# mouse_v4.net
KiCad netlist of a schematic drawn in EAGLE
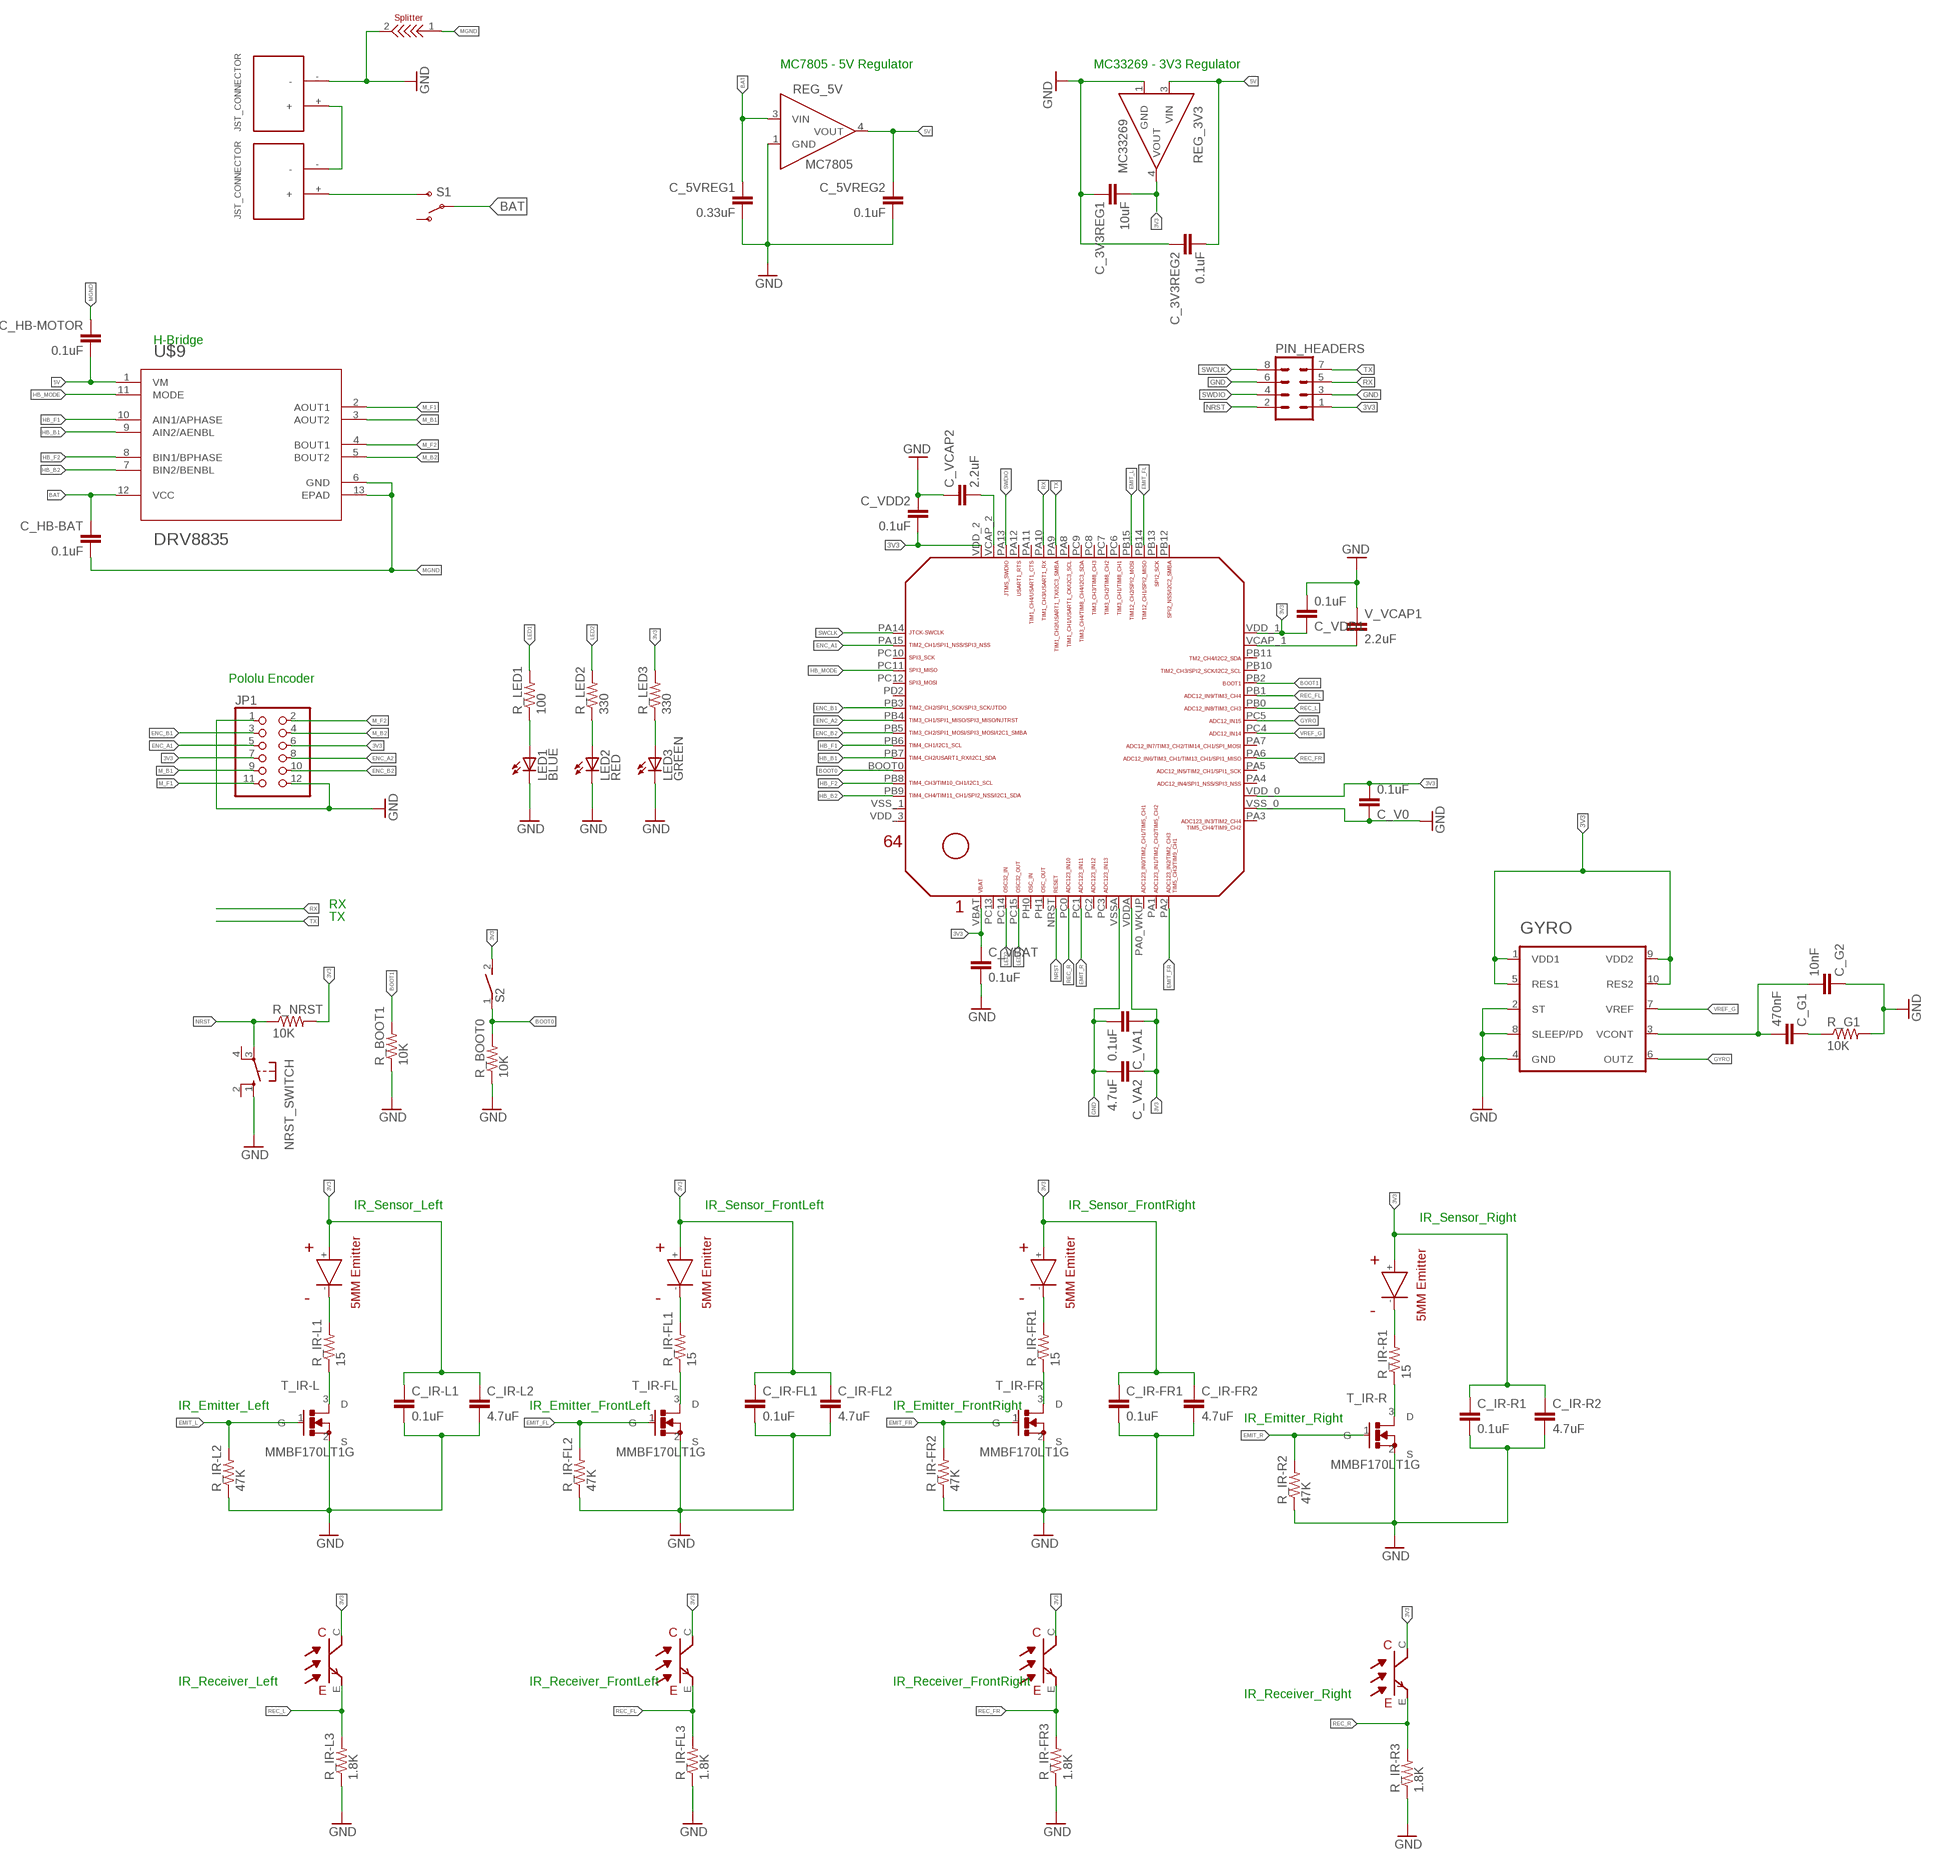
[diagram p0: schematic, sheet 1]

(export (version "E")
  (design (tool "Eeschema 10.0.6"))
  (components
    (comp (ref "C_3V3REG1")
      (value "10uF")
      (footprint "eagle-import:0603-CAP")
      (libsource (lib "eagle-import") (part "CAP0603-CAP"))
    )
    (comp (ref "C_3V3REG2")
      (value "0.1uF")
      (footprint "eagle-import:0603-CAP")
      (libsource (lib "eagle-import") (part "CAP0603-CAP"))
    )
    (comp (ref "C_5VREG1")
      (value "0.33uF")
      (footprint "eagle-import:0603-CAP")
      (libsource (lib "eagle-import") (part "CAP0603-CAP"))
    )
    (comp (ref "C_5VREG2")
      (value "0.1uF")
      (footprint "eagle-import:0603-CAP")
      (libsource (lib "eagle-import") (part "CAP0603-CAP"))
    )
    (comp (ref "C_G1")
      (value "470nF")
      (footprint "eagle-import:0603-CAP")
      (libsource (lib "eagle-import") (part "CAP0603-CAP"))
    )
    (comp (ref "C_G2")
      (value "10nF")
      (footprint "eagle-import:0603-CAP")
      (libsource (lib "eagle-import") (part "CAP0603-CAP"))
    )
    (comp (ref "C_HB-BAT")
      (value "0.1uF")
      (footprint "eagle-import:0603-CAP")
      (libsource (lib "eagle-import") (part "CAP0603-CAP"))
    )
    (comp (ref "C_HB-MOTOR")
      (value "0.1uF")
      (footprint "eagle-import:0603-CAP")
      (libsource (lib "eagle-import") (part "CAP0603-CAP"))
    )
    (comp (ref "C_IR-FL1")
      (value "0.1uF")
      (footprint "eagle-import:0603-CAP")
      (libsource (lib "eagle-import") (part "CAP0603-CAP"))
    )
    (comp (ref "C_IR-FL2")
      (value "4.7uF")
      (footprint "eagle-import:0603-CAP")
      (libsource (lib "eagle-import") (part "CAP0603-CAP"))
    )
    (comp (ref "C_IR-FR1")
      (value "0.1uF")
      (footprint "eagle-import:0603-CAP")
      (libsource (lib "eagle-import") (part "CAP0603-CAP"))
    )
    (comp (ref "C_IR-FR2")
      (value "4.7uF")
      (footprint "eagle-import:0603-CAP")
      (libsource (lib "eagle-import") (part "CAP0603-CAP"))
    )
    (comp (ref "C_IR-L1")
      (value "0.1uF")
      (footprint "eagle-import:0603-CAP")
      (libsource (lib "eagle-import") (part "CAP0603-CAP"))
    )
    (comp (ref "C_IR-L2")
      (value "4.7uF")
      (footprint "eagle-import:0603-CAP")
      (libsource (lib "eagle-import") (part "CAP0603-CAP"))
    )
    (comp (ref "C_IR-R1")
      (value "0.1uF")
      (footprint "eagle-import:0603-CAP")
      (libsource (lib "eagle-import") (part "CAP0603-CAP"))
    )
    (comp (ref "C_IR-R2")
      (value "4.7uF")
      (footprint "eagle-import:0603-CAP")
      (libsource (lib "eagle-import") (part "CAP0603-CAP"))
    )
    (comp (ref "C_V0")
      (value "0.1uF")
      (footprint "eagle-import:0603-CAP")
      (libsource (lib "eagle-import") (part "CAP0603-CAP"))
    )
    (comp (ref "C_VA1")
      (value "0.1uF")
      (footprint "eagle-import:0603-CAP")
      (libsource (lib "eagle-import") (part "CAP0603-CAP"))
    )
    (comp (ref "C_VA2")
      (value "4.7uF")
      (footprint "eagle-import:0603-CAP")
      (libsource (lib "eagle-import") (part "CAP0603-CAP"))
    )
    (comp (ref "C_VBAT")
      (value "0.1uF")
      (footprint "eagle-import:0603-CAP")
      (libsource (lib "eagle-import") (part "CAP0603-CAP"))
    )
    (comp (ref "C_VCAP2")
      (value "2.2uF")
      (footprint "eagle-import:0603-CAP")
      (libsource (lib "eagle-import") (part "CAP0603-CAP"))
    )
    (comp (ref "C_VDD1")
      (value "0.1uF")
      (footprint "eagle-import:0603-CAP")
      (libsource (lib "eagle-import") (part "CAP0603-CAP"))
    )
    (comp (ref "C_VDD2")
      (value "0.1uF")
      (footprint "eagle-import:0603-CAP")
      (libsource (lib "eagle-import") (part "CAP0603-CAP"))
    )
    (comp (ref "GYRO")
      (value "LY3200ALH")
      (footprint "eagle-import:10-TLGA")
      (libsource (lib "eagle-import") (part "LY3200ALH"))
    )
    (comp (ref "IR_FL")
      (value "EMITTER")
      (footprint "eagle-import:EMITTER")
      (libsource (lib "eagle-import") (part "EMITTER"))
    )
    (comp (ref "IR_FR")
      (value "EMITTER")
      (footprint "eagle-import:EMITTER")
      (libsource (lib "eagle-import") (part "EMITTER"))
    )
    (comp (ref "IR_L")
      (value "EMITTER")
      (footprint "eagle-import:EMITTER")
      (libsource (lib "eagle-import") (part "EMITTER"))
    )
    (comp (ref "IR_R")
      (value "EMITTER")
      (footprint "eagle-import:EMITTER")
      (libsource (lib "eagle-import") (part "EMITTER"))
    )
    (comp (ref "JP1")
      (value "PINHD-2X6")
      (footprint "eagle-import:2X06")
      (libsource (lib "eagle-import") (part "PINHD-2X6"))
    )
    (comp (ref "LED1")
      (value "BLUE")
      (footprint "eagle-import:CHIPLED_0603")
      (libsource (lib "eagle-import") (part "LEDCHIPLED_0603"))
    )
    (comp (ref "LED2")
      (value "RED")
      (footprint "eagle-import:CHIPLED_0603")
      (libsource (lib "eagle-import") (part "LEDCHIPLED_0603"))
    )
    (comp (ref "LED3")
      (value "GREEN")
      (footprint "eagle-import:CHIPLED_0603")
      (libsource (lib "eagle-import") (part "LEDCHIPLED_0603"))
    )
    (comp (ref "NRST_SWITCH")
      (value "10-XX")
      (footprint "eagle-import:B3F-10XX")
      (fields (field (name "MPN") "B3F-1000"))
      (libsource (lib "eagle-import") (part "10-XX"))
    )
    (comp (ref "PIN_HEADERS")
      (value "MA04-2")
      (footprint "eagle-import:MA04-2")
      (libsource (lib "eagle-import") (part "MA04-2"))
    )
    (comp (ref "REG_3V3")
      (value "MC33269")
      (footprint "eagle-import:TO-252-3")
      (libsource (lib "eagle-import") (part "MC33269"))
    )
    (comp (ref "REG_5V")
      (value "MC7805")
      (footprint "eagle-import:TO-252-3")
      (libsource (lib "eagle-import") (part "MC7805"))
    )
    (comp (ref "R_BOOT0")
      (value "10K")
      (footprint "eagle-import:0603-RES")
      (libsource (lib "eagle-import") (part "1.8KOHM1/10W1%(0603)"))
    )
    (comp (ref "R_BOOT1")
      (value "10K")
      (footprint "eagle-import:0603-RES")
      (libsource (lib "eagle-import") (part "1.8KOHM1/10W1%(0603)"))
    )
    (comp (ref "R_G1")
      (value "10K")
      (footprint "eagle-import:0603-RES")
      (libsource (lib "eagle-import") (part "1.8KOHM1/10W1%(0603)"))
    )
    (comp (ref "R_IR-FL1")
      (value "15")
      (footprint "eagle-import:0603-RES")
      (libsource (lib "eagle-import") (part "1.8KOHM1/10W1%(0603)"))
    )
    (comp (ref "R_IR-FL2")
      (value "47K")
      (footprint "eagle-import:0603-RES")
      (libsource (lib "eagle-import") (part "1.8KOHM1/10W1%(0603)"))
    )
    (comp (ref "R_IR-FL3")
      (value "1.8K")
      (footprint "eagle-import:0603-RES")
      (libsource (lib "eagle-import") (part "1.8KOHM1/10W1%(0603)"))
    )
    (comp (ref "R_IR-FR1")
      (value "15")
      (footprint "eagle-import:0603-RES")
      (libsource (lib "eagle-import") (part "1.8KOHM1/10W1%(0603)"))
    )
    (comp (ref "R_IR-FR2")
      (value "47K")
      (footprint "eagle-import:0603-RES")
      (libsource (lib "eagle-import") (part "1.8KOHM1/10W1%(0603)"))
    )
    (comp (ref "R_IR-FR3")
      (value "1.8K")
      (footprint "eagle-import:0603-RES")
      (libsource (lib "eagle-import") (part "1.8KOHM1/10W1%(0603)"))
    )
    (comp (ref "R_IR-L1")
      (value "15")
      (footprint "eagle-import:0603-RES")
      (libsource (lib "eagle-import") (part "1.8KOHM1/10W1%(0603)"))
    )
    (comp (ref "R_IR-L2")
      (value "47K")
      (footprint "eagle-import:0603-RES")
      (libsource (lib "eagle-import") (part "1.8KOHM1/10W1%(0603)"))
    )
    (comp (ref "R_IR-L3")
      (value "1.8K")
      (footprint "eagle-import:0603-RES")
      (libsource (lib "eagle-import") (part "1.8KOHM1/10W1%(0603)"))
    )
    (comp (ref "R_IR-R1")
      (value "15")
      (footprint "eagle-import:0603-RES")
      (libsource (lib "eagle-import") (part "1.8KOHM1/10W1%(0603)"))
    )
    (comp (ref "R_IR-R2")
      (value "47K")
      (footprint "eagle-import:0603-RES")
      (libsource (lib "eagle-import") (part "1.8KOHM1/10W1%(0603)"))
    )
    (comp (ref "R_IR-R3")
      (value "1.8K")
      (footprint "eagle-import:0603-RES")
      (libsource (lib "eagle-import") (part "1.8KOHM1/10W1%(0603)"))
    )
    (comp (ref "R_LED1")
      (value "100")
      (footprint "eagle-import:0603-RES")
      (libsource (lib "eagle-import") (part "1.8KOHM1/10W1%(0603)"))
    )
    (comp (ref "R_LED2")
      (value "330")
      (footprint "eagle-import:0603-RES")
      (libsource (lib "eagle-import") (part "1.8KOHM1/10W1%(0603)"))
    )
    (comp (ref "R_LED3")
      (value "330")
      (footprint "eagle-import:0603-RES")
      (libsource (lib "eagle-import") (part "1.8KOHM1/10W1%(0603)"))
    )
    (comp (ref "R_NRST")
      (value "10K")
      (footprint "eagle-import:0603-RES")
      (libsource (lib "eagle-import") (part "1.8KOHM1/10W1%(0603)"))
    )
    (comp (ref "S1")
      (value "SWITCH-SPSTKIT")
      (footprint "eagle-import:SWITCH-SPDT_KIT")
      (libsource (lib "eagle-import") (part "SWITCH-SPSTKIT"))
    )
    (comp (ref "S2")
      (value "DS01E")
      (footprint "eagle-import:DS-01")
      (libsource (lib "eagle-import") (part "DS01E"))
    )
    (comp (ref "T_IR-FL")
      (value "MMBF170LT1G")
      (footprint "eagle-import:SOT-23")
      (libsource (lib "eagle-import") (part "MMBF170LT1G"))
    )
    (comp (ref "T_IR-FR")
      (value "MMBF170LT1G")
      (footprint "eagle-import:SOT-23")
      (libsource (lib "eagle-import") (part "MMBF170LT1G"))
    )
    (comp (ref "T_IR-L")
      (value "MMBF170LT1G")
      (footprint "eagle-import:SOT-23")
      (libsource (lib "eagle-import") (part "MMBF170LT1G"))
    )
    (comp (ref "T_IR-R")
      (value "MMBF170LT1G")
      (footprint "eagle-import:SOT-23")
      (libsource (lib "eagle-import") (part "MMBF170LT1G"))
    )
    (comp (ref "U$1")
      (value "STM32F405/415_LQFP64")
      (footprint "eagle-import:STM32F405_415_LQFP64")
      (libsource (lib "eagle-import") (part "STM32F405/415_LQFP64"))
    )
    (comp (ref "U$2")
      (value "JST_CONNECTOR_FEMALE")
      (footprint "eagle-import:JST_CONNECTOR_FEMALE")
      (libsource (lib "eagle-import") (part "JST_CONNECTOR_FEMALE"))
    )
    (comp (ref "U$3")
      (value "JST_CONNECTOR_FEMALE")
      (footprint "eagle-import:JST_CONNECTOR_FEMALE")
      (libsource (lib "eagle-import") (part "JST_CONNECTOR_FEMALE"))
    )
    (comp (ref "U$4")
      (value "RECEIVER")
      (footprint "eagle-import:RECEIVER")
      (libsource (lib "eagle-import") (part "RECEIVER"))
    )
    (comp (ref "U$5")
      (value "RECEIVER")
      (footprint "eagle-import:RECEIVER")
      (libsource (lib "eagle-import") (part "RECEIVER"))
    )
    (comp (ref "U$6")
      (value "RECEIVER")
      (footprint "eagle-import:RECEIVER")
      (libsource (lib "eagle-import") (part "RECEIVER"))
    )
    (comp (ref "U$7")
      (value "RECEIVER")
      (footprint "eagle-import:RECEIVER")
      (libsource (lib "eagle-import") (part "RECEIVER"))
    )
    (comp (ref "U$8")
      (value "SPLITTER")
      (footprint "eagle-import:SPLITTER")
      (libsource (lib "eagle-import") (part "SPLITTER"))
    )
    (comp (ref "U$9")
      (value "DRV8835")
      (footprint "eagle-import:12-WFDFN")
      (libsource (lib "eagle-import") (part "DRV8835"))
    )
    (comp (ref "V_VCAP1")
      (value "2.2uF")
      (footprint "eagle-import:0603-CAP")
      (libsource (lib "eagle-import") (part "CAP0603-CAP"))
    )
  )
  (nets
    (net (code "1") (name "3V3") (class "Default")
      (node (ref "C_3V3REG1") (pin "2") (pinfunction "2_2") (pintype "passive"))
      (node (ref "C_IR-FL1") (pin "1") (pinfunction "1_1") (pintype "passive"))
      (node (ref "C_IR-FL2") (pin "1") (pinfunction "1_1") (pintype "passive"))
      (node (ref "C_IR-FR1") (pin "1") (pinfunction "1_1") (pintype "passive"))
      (node (ref "C_IR-FR2") (pin "1") (pinfunction "1_1") (pintype "passive"))
      (node (ref "C_IR-L1") (pin "1") (pinfunction "1_1") (pintype "passive"))
      (node (ref "C_IR-L2") (pin "1") (pinfunction "1_1") (pintype "passive"))
      (node (ref "C_IR-R1") (pin "1") (pinfunction "1_1") (pintype "passive"))
      (node (ref "C_IR-R2") (pin "1") (pinfunction "1_1") (pintype "passive"))
      (node (ref "C_V0") (pin "2") (pinfunction "2_2") (pintype "passive"))
      (node (ref "C_VA1") (pin "1") (pinfunction "1_1") (pintype "passive"))
      (node (ref "C_VA2") (pin "1") (pinfunction "1_1") (pintype "passive"))
      (node (ref "C_VBAT") (pin "1") (pinfunction "1_1") (pintype "passive"))
      (node (ref "C_VDD1") (pin "1") (pinfunction "1_1") (pintype "passive"))
      (node (ref "C_VDD2") (pin "2") (pinfunction "2_2") (pintype "passive"))
      (node (ref "GYRO") (pin "1") (pinfunction "VDD1_1") (pintype "bidirectional"))
      (node (ref "GYRO") (pin "10") (pinfunction "RES2_10") (pintype "bidirectional"))
      (node (ref "GYRO") (pin "5") (pinfunction "RES1_5") (pintype "bidirectional"))
      (node (ref "GYRO") (pin "9") (pinfunction "VDD2_9") (pintype "bidirectional"))
      (node (ref "IR_FL") (pin "+") (pinfunction "+_+") (pintype "bidirectional"))
      (node (ref "IR_FR") (pin "+") (pinfunction "+_+") (pintype "bidirectional"))
      (node (ref "IR_L") (pin "+") (pinfunction "+_+") (pintype "bidirectional"))
      (node (ref "IR_R") (pin "+") (pinfunction "+_+") (pintype "bidirectional"))
      (node (ref "JP1") (pin "6") (pinfunction "6_6") (pintype "passive"))
      (node (ref "JP1") (pin "7") (pinfunction "7_7") (pintype "passive"))
      (node (ref "PIN_HEADERS") (pin "1") (pinfunction "1_1") (pintype "passive"))
      (node (ref "REG_3V3") (pin "4") (pinfunction "VOUT_4") (pintype "bidirectional"))
      (node (ref "R_LED3") (pin "2") (pinfunction "2_2") (pintype "passive"))
      (node (ref "R_NRST") (pin "2") (pinfunction "2_2") (pintype "passive"))
      (node (ref "S2") (pin "2") (pinfunction "2_2") (pintype "passive"))
      (node (ref "U$1") (pin "VBAT") (pinfunction "VBAT_VBAT") (pintype "bidirectional"))
      (node (ref "U$1") (pin "VDDA") (pinfunction "VDDA_VDDA") (pintype "bidirectional"))
      (node (ref "U$1") (pin "VDD_0") (pinfunction "VDD_0_VDD_0") (pintype "bidirectional"))
      (node (ref "U$1") (pin "VDD_1") (pinfunction "VDD_1_VDD_1") (pintype "bidirectional"))
      (node (ref "U$1") (pin "VDD_2") (pinfunction "VDD_2_VDD_2") (pintype "bidirectional"))
      (node (ref "U$4") (pin "C") (pinfunction "C_C") (pintype "bidirectional"))
      (node (ref "U$5") (pin "C") (pinfunction "C_C") (pintype "bidirectional"))
      (node (ref "U$6") (pin "C") (pinfunction "C_C") (pintype "bidirectional"))
      (node (ref "U$7") (pin "C") (pinfunction "C_C") (pintype "bidirectional"))
    )
    (net (code "2") (name "5V") (class "Default")
      (node (ref "C_3V3REG2") (pin "2") (pinfunction "2_2") (pintype "passive"))
      (node (ref "C_5VREG2") (pin "1") (pinfunction "1_1") (pintype "passive"))
      (node (ref "C_HB-MOTOR") (pin "2") (pinfunction "2_2") (pintype "passive"))
      (node (ref "REG_3V3") (pin "3") (pinfunction "VIN_3") (pintype "bidirectional"))
      (node (ref "REG_5V") (pin "4") (pinfunction "VOUT_4") (pintype "bidirectional"))
      (node (ref "U$9") (pin "1") (pinfunction "VM_1") (pintype "bidirectional"))
    )
    (net (code "3") (name "BAT") (class "Default")
      (node (ref "C_5VREG1") (pin "1") (pinfunction "1_1") (pintype "passive"))
      (node (ref "C_HB-BAT") (pin "1") (pinfunction "1_1") (pintype "passive"))
      (node (ref "REG_5V") (pin "3") (pinfunction "VIN_3") (pintype "bidirectional"))
      (node (ref "S1") (pin "2") (pinfunction "P_2") (pintype "passive"))
      (node (ref "U$9") (pin "12") (pinfunction "VCC_12") (pintype "bidirectional"))
    )
    (net (code "4") (name "BOOT0") (class "Default")
      (node (ref "R_BOOT0") (pin "2") (pinfunction "2_2") (pintype "passive"))
      (node (ref "S2") (pin "1") (pinfunction "1_1") (pintype "passive"))
      (node (ref "U$1") (pin "BOOT0") (pinfunction "BOOT0_BOOT0") (pintype "bidirectional"))
    )
    (net (code "5") (name "BOOT1") (class "Default")
      (node (ref "R_BOOT1") (pin "2") (pinfunction "2_2") (pintype "passive"))
      (node (ref "U$1") (pin "PB2") (pinfunction "PB2_PB2") (pintype "bidirectional"))
    )
    (net (code "6") (name "EMIT_FL") (class "Default")
      (node (ref "R_IR-FL2") (pin "2") (pinfunction "2_2") (pintype "passive"))
      (node (ref "T_IR-FL") (pin "1") (pinfunction "G_1") (pintype "passive"))
      (node (ref "U$1") (pin "PB14") (pinfunction "PB14_PB14") (pintype "bidirectional"))
    )
    (net (code "7") (name "EMIT_FR") (class "Default")
      (node (ref "R_IR-FR2") (pin "2") (pinfunction "2_2") (pintype "passive"))
      (node (ref "T_IR-FR") (pin "1") (pinfunction "G_1") (pintype "passive"))
      (node (ref "U$1") (pin "PA2") (pinfunction "PA2_PA2") (pintype "bidirectional"))
    )
    (net (code "8") (name "EMIT_L") (class "Default")
      (node (ref "R_IR-L2") (pin "2") (pinfunction "2_2") (pintype "passive"))
      (node (ref "T_IR-L") (pin "1") (pinfunction "G_1") (pintype "passive"))
      (node (ref "U$1") (pin "PB15") (pinfunction "PB15_PB15") (pintype "bidirectional"))
    )
    (net (code "9") (name "EMIT_R") (class "Default")
      (node (ref "R_IR-R2") (pin "2") (pinfunction "2_2") (pintype "passive"))
      (node (ref "T_IR-R") (pin "1") (pinfunction "G_1") (pintype "passive"))
      (node (ref "U$1") (pin "PC1") (pinfunction "PC1_PC1") (pintype "bidirectional"))
    )
    (net (code "10") (name "ENC_A1") (class "Default")
      (node (ref "JP1") (pin "5") (pinfunction "5_5") (pintype "passive"))
      (node (ref "U$1") (pin "PA15") (pinfunction "PA15_PA15") (pintype "bidirectional"))
    )
    (net (code "11") (name "ENC_A2") (class "Default")
      (node (ref "JP1") (pin "8") (pinfunction "8_8") (pintype "passive"))
      (node (ref "U$1") (pin "PB4") (pinfunction "PB4_PB4") (pintype "bidirectional"))
    )
    (net (code "12") (name "ENC_B1") (class "Default")
      (node (ref "JP1") (pin "3") (pinfunction "3_3") (pintype "passive"))
      (node (ref "U$1") (pin "PB3") (pinfunction "PB3_PB3") (pintype "bidirectional"))
    )
    (net (code "13") (name "ENC_B2") (class "Default")
      (node (ref "JP1") (pin "10") (pinfunction "10_10") (pintype "passive"))
      (node (ref "U$1") (pin "PB5") (pinfunction "PB5_PB5") (pintype "bidirectional"))
    )
    (net (code "14") (name "GND") (class "Default")
      (node (ref "C_3V3REG1") (pin "1") (pinfunction "1_1") (pintype "passive"))
      (node (ref "C_3V3REG2") (pin "1") (pinfunction "1_1") (pintype "passive"))
      (node (ref "C_5VREG1") (pin "2") (pinfunction "2_2") (pintype "passive"))
      (node (ref "C_5VREG2") (pin "2") (pinfunction "2_2") (pintype "passive"))
      (node (ref "C_G2") (pin "1") (pinfunction "1_1") (pintype "passive"))
      (node (ref "C_IR-FL1") (pin "2") (pinfunction "2_2") (pintype "passive"))
      (node (ref "C_IR-FL2") (pin "2") (pinfunction "2_2") (pintype "passive"))
      (node (ref "C_IR-FR1") (pin "2") (pinfunction "2_2") (pintype "passive"))
      (node (ref "C_IR-FR2") (pin "2") (pinfunction "2_2") (pintype "passive"))
      (node (ref "C_IR-L1") (pin "2") (pinfunction "2_2") (pintype "passive"))
      (node (ref "C_IR-L2") (pin "2") (pinfunction "2_2") (pintype "passive"))
      (node (ref "C_IR-R1") (pin "2") (pinfunction "2_2") (pintype "passive"))
      (node (ref "C_IR-R2") (pin "2") (pinfunction "2_2") (pintype "passive"))
      (node (ref "C_V0") (pin "1") (pinfunction "1_1") (pintype "passive"))
      (node (ref "C_VA1") (pin "2") (pinfunction "2_2") (pintype "passive"))
      (node (ref "C_VA2") (pin "2") (pinfunction "2_2") (pintype "passive"))
      (node (ref "C_VBAT") (pin "2") (pinfunction "2_2") (pintype "passive"))
      (node (ref "C_VCAP2") (pin "1") (pinfunction "1_1") (pintype "passive"))
      (node (ref "C_VDD1") (pin "2") (pinfunction "2_2") (pintype "passive"))
      (node (ref "C_VDD2") (pin "1") (pinfunction "1_1") (pintype "passive"))
      (node (ref "GYRO") (pin "2") (pinfunction "ST_2") (pintype "bidirectional"))
      (node (ref "GYRO") (pin "4") (pinfunction "GND_4") (pintype "bidirectional"))
      (node (ref "GYRO") (pin "8") (pinfunction "SLEEP/PD_8") (pintype "bidirectional"))
      (node (ref "JP1") (pin "1") (pinfunction "1_1") (pintype "passive"))
      (node (ref "JP1") (pin "12") (pinfunction "12_12") (pintype "passive"))
      (node (ref "LED1") (pin "C") (pinfunction "C_C") (pintype "passive"))
      (node (ref "LED2") (pin "C") (pinfunction "C_C") (pintype "passive"))
      (node (ref "LED3") (pin "C") (pinfunction "C_C") (pintype "passive"))
      (node (ref "NRST_SWITCH") (pin "1") (pinfunction "S_1") (pintype "passive"))
      (node (ref "PIN_HEADERS") (pin "3") (pinfunction "3_3") (pintype "passive"))
      (node (ref "PIN_HEADERS") (pin "6") (pinfunction "6_6") (pintype "passive"))
      (node (ref "REG_3V3") (pin "1") (pinfunction "GND_1") (pintype "bidirectional"))
      (node (ref "REG_5V") (pin "1") (pinfunction "GND_1") (pintype "bidirectional"))
      (node (ref "R_BOOT0") (pin "1") (pinfunction "1_1") (pintype "passive"))
      (node (ref "R_BOOT1") (pin "1") (pinfunction "1_1") (pintype "passive"))
      (node (ref "R_G1") (pin "2") (pinfunction "2_2") (pintype "passive"))
      (node (ref "R_IR-FL2") (pin "1") (pinfunction "1_1") (pintype "passive"))
      (node (ref "R_IR-FL3") (pin "1") (pinfunction "1_1") (pintype "passive"))
      (node (ref "R_IR-FR2") (pin "1") (pinfunction "1_1") (pintype "passive"))
      (node (ref "R_IR-FR3") (pin "1") (pinfunction "1_1") (pintype "passive"))
      (node (ref "R_IR-L2") (pin "1") (pinfunction "1_1") (pintype "passive"))
      (node (ref "R_IR-L3") (pin "1") (pinfunction "1_1") (pintype "passive"))
      (node (ref "R_IR-R2") (pin "1") (pinfunction "1_1") (pintype "passive"))
      (node (ref "R_IR-R3") (pin "1") (pinfunction "1_1") (pintype "passive"))
      (node (ref "T_IR-FL") (pin "2") (pinfunction "S_2") (pintype "passive"))
      (node (ref "T_IR-FR") (pin "2") (pinfunction "S_2") (pintype "passive"))
      (node (ref "T_IR-L") (pin "2") (pinfunction "S_2") (pintype "passive"))
      (node (ref "T_IR-R") (pin "2") (pinfunction "S_2") (pintype "passive"))
      (node (ref "U$1") (pin "VSSA") (pinfunction "VSSA_VSSA") (pintype "bidirectional"))
      (node (ref "U$1") (pin "VSS_0") (pinfunction "VSS_0_VSS_0") (pintype "bidirectional"))
      (node (ref "U$2") (pin "-") (pinfunction "-_-") (pintype "bidirectional"))
      (node (ref "U$8") (pin "2") (pinfunction "2_2") (pintype "bidirectional"))
      (node (ref "V_VCAP1") (pin "1") (pinfunction "1_1") (pintype "passive"))
    )
    (net (code "15") (name "GYRO") (class "Default")
      (node (ref "GYRO") (pin "6") (pinfunction "OUTZ_6") (pintype "bidirectional"))
      (node (ref "U$1") (pin "PC5") (pinfunction "PC5_PC5") (pintype "bidirectional"))
    )
    (net (code "16") (name "HB_B1") (class "Default")
      (node (ref "U$1") (pin "PB7") (pinfunction "PB7_PB7") (pintype "bidirectional"))
      (node (ref "U$9") (pin "9") (pinfunction "AIN2/AENBL_9") (pintype "bidirectional"))
    )
    (net (code "17") (name "HB_B2") (class "Default")
      (node (ref "U$1") (pin "PB9") (pinfunction "PB9_PB9") (pintype "bidirectional"))
      (node (ref "U$9") (pin "7") (pinfunction "BIN2/BENBL_7") (pintype "bidirectional"))
    )
    (net (code "18") (name "HB_F1") (class "Default")
      (node (ref "U$1") (pin "PB6") (pinfunction "PB6_PB6") (pintype "bidirectional"))
      (node (ref "U$9") (pin "10") (pinfunction "AIN1/APHASE_10") (pintype "bidirectional"))
    )
    (net (code "19") (name "HB_F2") (class "Default")
      (node (ref "U$1") (pin "PB8") (pinfunction "PB8_PB8") (pintype "bidirectional"))
      (node (ref "U$9") (pin "8") (pinfunction "BIN1/BPHASE_8") (pintype "bidirectional"))
    )
    (net (code "20") (name "HB_MODE") (class "Default")
      (node (ref "U$1") (pin "PC11") (pinfunction "PC11_PC11") (pintype "bidirectional"))
      (node (ref "U$9") (pin "11") (pinfunction "MODE_11") (pintype "bidirectional"))
    )
    (net (code "21") (name "LED1") (class "Default")
      (node (ref "R_LED1") (pin "2") (pinfunction "2_2") (pintype "passive"))
      (node (ref "U$1") (pin "PC15") (pinfunction "PC15_PC15") (pintype "bidirectional"))
    )
    (net (code "22") (name "LED2") (class "Default")
      (node (ref "R_LED2") (pin "2") (pinfunction "2_2") (pintype "passive"))
      (node (ref "U$1") (pin "PC14") (pinfunction "PC14_PC14") (pintype "bidirectional"))
    )
    (net (code "23") (name "MGND") (class "Default")
      (node (ref "C_HB-BAT") (pin "2") (pinfunction "2_2") (pintype "passive"))
      (node (ref "C_HB-MOTOR") (pin "1") (pinfunction "1_1") (pintype "passive"))
      (node (ref "U$8") (pin "1") (pinfunction "1_1") (pintype "bidirectional"))
      (node (ref "U$9") (pin "13") (pinfunction "EPAD_13") (pintype "bidirectional"))
      (node (ref "U$9") (pin "6") (pinfunction "GND_6") (pintype "bidirectional"))
    )
    (net (code "24") (name "M_B1") (class "Default")
      (node (ref "JP1") (pin "9") (pinfunction "9_9") (pintype "passive"))
      (node (ref "U$9") (pin "3") (pinfunction "AOUT2_3") (pintype "bidirectional"))
    )
    (net (code "25") (name "M_B2") (class "Default")
      (node (ref "JP1") (pin "4") (pinfunction "4_4") (pintype "passive"))
      (node (ref "U$9") (pin "5") (pinfunction "BOUT2_5") (pintype "bidirectional"))
    )
    (net (code "26") (name "M_F1") (class "Default")
      (node (ref "JP1") (pin "11") (pinfunction "11_11") (pintype "passive"))
      (node (ref "U$9") (pin "2") (pinfunction "AOUT1_2") (pintype "bidirectional"))
    )
    (net (code "27") (name "M_F2") (class "Default")
      (node (ref "JP1") (pin "2") (pinfunction "2_2") (pintype "passive"))
      (node (ref "U$9") (pin "4") (pinfunction "BOUT1_4") (pintype "bidirectional"))
    )
    (net (code "28") (name "NRST") (class "Default")
      (node (ref "NRST_SWITCH") (pin "3") (pinfunction "P_3") (pintype "passive"))
      (node (ref "PIN_HEADERS") (pin "2") (pinfunction "2_2") (pintype "passive"))
      (node (ref "R_NRST") (pin "1") (pinfunction "1_1") (pintype "passive"))
      (node (ref "U$1") (pin "NRST") (pinfunction "NRST_NRST") (pintype "bidirectional"))
    )
    (net (code "29") (name "Net-(C_G1-Pad1)") (class "Default")
      (node (ref "C_G1") (pin "1") (pinfunction "1_1") (pintype "passive"))
      (node (ref "R_G1") (pin "1") (pinfunction "1_1") (pintype "passive"))
    )
    (net (code "30") (name "Net-(C_VCAP2-Pad2)") (class "Default")
      (node (ref "C_VCAP2") (pin "2") (pinfunction "2_2") (pintype "passive"))
      (node (ref "U$1") (pin "VCAP_2") (pinfunction "VCAP_2_VCAP_2") (pintype "bidirectional"))
    )
    (net (code "31") (name "Net-(GYRO-VCONT)") (class "Default")
      (node (ref "C_G1") (pin "2") (pinfunction "2_2") (pintype "passive"))
      (node (ref "C_G2") (pin "2") (pinfunction "2_2") (pintype "passive"))
      (node (ref "GYRO") (pin "3") (pinfunction "VCONT_3") (pintype "bidirectional"))
    )
    (net (code "32") (name "Net-(IR_FL-Pad-)") (class "Default")
      (node (ref "IR_FL") (pin "-") (pinfunction "-_-") (pintype "bidirectional"))
      (node (ref "R_IR-FL1") (pin "2") (pinfunction "2_2") (pintype "passive"))
    )
    (net (code "33") (name "Net-(IR_FR-Pad-)") (class "Default")
      (node (ref "IR_FR") (pin "-") (pinfunction "-_-") (pintype "bidirectional"))
      (node (ref "R_IR-FR1") (pin "2") (pinfunction "2_2") (pintype "passive"))
    )
    (net (code "34") (name "Net-(IR_L-Pad-)") (class "Default")
      (node (ref "IR_L") (pin "-") (pinfunction "-_-") (pintype "bidirectional"))
      (node (ref "R_IR-L1") (pin "2") (pinfunction "2_2") (pintype "passive"))
    )
    (net (code "35") (name "Net-(IR_R-Pad-)") (class "Default")
      (node (ref "IR_R") (pin "-") (pinfunction "-_-") (pintype "bidirectional"))
      (node (ref "R_IR-R1") (pin "2") (pinfunction "2_2") (pintype "passive"))
    )
    (net (code "36") (name "Net-(LED1-PadA)") (class "Default")
      (node (ref "LED1") (pin "A") (pinfunction "A_A") (pintype "passive"))
      (node (ref "R_LED1") (pin "1") (pinfunction "1_1") (pintype "passive"))
    )
    (net (code "37") (name "Net-(LED2-PadA)") (class "Default")
      (node (ref "LED2") (pin "A") (pinfunction "A_A") (pintype "passive"))
      (node (ref "R_LED2") (pin "1") (pinfunction "1_1") (pintype "passive"))
    )
    (net (code "38") (name "Net-(LED3-PadA)") (class "Default")
      (node (ref "LED3") (pin "A") (pinfunction "A_A") (pintype "passive"))
      (node (ref "R_LED3") (pin "1") (pinfunction "1_1") (pintype "passive"))
    )
    (net (code "39") (name "Net-(S1-S)") (class "Default")
      (node (ref "S1") (pin "3") (pinfunction "S_3") (pintype "passive"))
      (node (ref "U$3") (pin "+") (pinfunction "+_+") (pintype "bidirectional"))
    )
    (net (code "40") (name "Net-(T_IR-FL-D)") (class "Default")
      (node (ref "R_IR-FL1") (pin "1") (pinfunction "1_1") (pintype "passive"))
      (node (ref "T_IR-FL") (pin "3") (pinfunction "D_3") (pintype "passive"))
    )
    (net (code "41") (name "Net-(T_IR-FR-D)") (class "Default")
      (node (ref "R_IR-FR1") (pin "1") (pinfunction "1_1") (pintype "passive"))
      (node (ref "T_IR-FR") (pin "3") (pinfunction "D_3") (pintype "passive"))
    )
    (net (code "42") (name "Net-(T_IR-L-D)") (class "Default")
      (node (ref "R_IR-L1") (pin "1") (pinfunction "1_1") (pintype "passive"))
      (node (ref "T_IR-L") (pin "3") (pinfunction "D_3") (pintype "passive"))
    )
    (net (code "43") (name "Net-(T_IR-R-D)") (class "Default")
      (node (ref "R_IR-R1") (pin "1") (pinfunction "1_1") (pintype "passive"))
      (node (ref "T_IR-R") (pin "3") (pinfunction "D_3") (pintype "passive"))
    )
    (net (code "44") (name "Net-(U$1-PadVCAP_1)") (class "Default")
      (node (ref "U$1") (pin "VCAP_1") (pinfunction "VCAP_1_VCAP_1") (pintype "bidirectional"))
      (node (ref "V_VCAP1") (pin "2") (pinfunction "2_2") (pintype "passive"))
    )
    (net (code "45") (name "Net-(U$2-Pad+)") (class "Default")
      (node (ref "U$2") (pin "+") (pinfunction "+_+") (pintype "bidirectional"))
      (node (ref "U$3") (pin "-") (pinfunction "-_-") (pintype "bidirectional"))
    )
    (net (code "46") (name "REC_FL") (class "Default")
      (node (ref "R_IR-FL3") (pin "2") (pinfunction "2_2") (pintype "passive"))
      (node (ref "U$1") (pin "PB1") (pinfunction "PB1_PB1") (pintype "bidirectional"))
      (node (ref "U$5") (pin "E") (pinfunction "E_E") (pintype "bidirectional"))
    )
    (net (code "47") (name "REC_FR") (class "Default")
      (node (ref "R_IR-FR3") (pin "2") (pinfunction "2_2") (pintype "passive"))
      (node (ref "U$1") (pin "PA6") (pinfunction "PA6_PA6") (pintype "bidirectional"))
      (node (ref "U$6") (pin "E") (pinfunction "E_E") (pintype "bidirectional"))
    )
    (net (code "48") (name "REC_L") (class "Default")
      (node (ref "R_IR-L3") (pin "2") (pinfunction "2_2") (pintype "passive"))
      (node (ref "U$1") (pin "PB0") (pinfunction "PB0_PB0") (pintype "bidirectional"))
      (node (ref "U$4") (pin "E") (pinfunction "E_E") (pintype "bidirectional"))
    )
    (net (code "49") (name "REC_R") (class "Default")
      (node (ref "R_IR-R3") (pin "2") (pinfunction "2_2") (pintype "passive"))
      (node (ref "U$1") (pin "PC0") (pinfunction "PC0_PC0") (pintype "bidirectional"))
      (node (ref "U$7") (pin "E") (pinfunction "E_E") (pintype "bidirectional"))
    )
    (net (code "50") (name "RX") (class "Default")
      (node (ref "PIN_HEADERS") (pin "5") (pinfunction "5_5") (pintype "passive"))
      (node (ref "U$1") (pin "PA10") (pinfunction "PA10_PA10") (pintype "bidirectional"))
    )
    (net (code "51") (name "SWCLK") (class "Default")
      (node (ref "PIN_HEADERS") (pin "8") (pinfunction "8_8") (pintype "passive"))
      (node (ref "U$1") (pin "PA14") (pinfunction "PA14_PA14") (pintype "bidirectional"))
    )
    (net (code "52") (name "SWDIO") (class "Default")
      (node (ref "PIN_HEADERS") (pin "4") (pinfunction "4_4") (pintype "passive"))
      (node (ref "U$1") (pin "PA13") (pinfunction "PA13_PA13") (pintype "bidirectional"))
    )
    (net (code "53") (name "TX") (class "Default")
      (node (ref "PIN_HEADERS") (pin "7") (pinfunction "7_7") (pintype "passive"))
      (node (ref "U$1") (pin "PA9") (pinfunction "PA9_PA9") (pintype "bidirectional"))
    )
    (net (code "54") (name "VREF_G") (class "Default")
      (node (ref "GYRO") (pin "7") (pinfunction "VREF_7") (pintype "bidirectional"))
      (node (ref "U$1") (pin "PC4") (pinfunction "PC4_PC4") (pintype "bidirectional"))
    )
    (net (code "55") (name "unconnected-(NRST_SWITCH-P1-Pad4)") (class "Default")
      (node (ref "NRST_SWITCH") (pin "4") (pinfunction "P1_4") (pintype "passive"))
    )
    (net (code "56") (name "unconnected-(NRST_SWITCH-S1-Pad2)") (class "Default")
      (node (ref "NRST_SWITCH") (pin "2") (pinfunction "S1_2") (pintype "passive"))
    )
    (net (code "57") (name "unconnected-(S1-O-Pad1)") (class "Default")
      (node (ref "S1") (pin "1") (pinfunction "O_1") (pintype "passive"))
    )
    (net (code "58") (name "unconnected-(U$1-PA0_AKUP-PadPA0_WKUP)") (class "Default")
      (node (ref "U$1") (pin "PA0_WKUP") (pinfunction "PA0_AKUP_PA0_WKUP") (pintype "bidirectional"))
    )
    (net (code "59") (name "unconnected-(U$1-PadPA1)") (class "Default")
      (node (ref "U$1") (pin "PA1") (pinfunction "PA1_PA1") (pintype "bidirectional"))
    )
    (net (code "60") (name "unconnected-(U$1-PadPA3)") (class "Default")
      (node (ref "U$1") (pin "PA3") (pinfunction "PA3_PA3") (pintype "bidirectional"))
    )
    (net (code "61") (name "unconnected-(U$1-PadPA4)") (class "Default")
      (node (ref "U$1") (pin "PA4") (pinfunction "PA4_PA4") (pintype "bidirectional"))
    )
    (net (code "62") (name "unconnected-(U$1-PadPA5)") (class "Default")
      (node (ref "U$1") (pin "PA5") (pinfunction "PA5_PA5") (pintype "bidirectional"))
    )
    (net (code "63") (name "unconnected-(U$1-PadPA7)") (class "Default")
      (node (ref "U$1") (pin "PA7") (pinfunction "PA7_PA7") (pintype "bidirectional"))
    )
    (net (code "64") (name "unconnected-(U$1-PadPA8)") (class "Default")
      (node (ref "U$1") (pin "PA8") (pinfunction "PA8_PA8") (pintype "bidirectional"))
    )
    (net (code "65") (name "unconnected-(U$1-PadPA11)") (class "Default")
      (node (ref "U$1") (pin "PA11") (pinfunction "PA11_PA11") (pintype "bidirectional"))
    )
    (net (code "66") (name "unconnected-(U$1-PadPA12)") (class "Default")
      (node (ref "U$1") (pin "PA12") (pinfunction "PA12_PA12") (pintype "bidirectional"))
    )
    (net (code "67") (name "unconnected-(U$1-PadPB10)") (class "Default")
      (node (ref "U$1") (pin "PB10") (pinfunction "PB10_PB10") (pintype "bidirectional"))
    )
    (net (code "68") (name "unconnected-(U$1-PadPB11)") (class "Default")
      (node (ref "U$1") (pin "PB11") (pinfunction "PB11_PB11") (pintype "bidirectional"))
    )
    (net (code "69") (name "unconnected-(U$1-PadPB12)") (class "Default")
      (node (ref "U$1") (pin "PB12") (pinfunction "PB12_PB12") (pintype "bidirectional"))
    )
    (net (code "70") (name "unconnected-(U$1-PadPB13)") (class "Default")
      (node (ref "U$1") (pin "PB13") (pinfunction "PB13_PB13") (pintype "bidirectional"))
    )
    (net (code "71") (name "unconnected-(U$1-PadPC2)") (class "Default")
      (node (ref "U$1") (pin "PC2") (pinfunction "PC2_PC2") (pintype "bidirectional"))
    )
    (net (code "72") (name "unconnected-(U$1-PadPC3)") (class "Default")
      (node (ref "U$1") (pin "PC3") (pinfunction "PC3_PC3") (pintype "bidirectional"))
    )
    (net (code "73") (name "unconnected-(U$1-PadPC6)") (class "Default")
      (node (ref "U$1") (pin "PC6") (pinfunction "PC6_PC6") (pintype "bidirectional"))
    )
    (net (code "74") (name "unconnected-(U$1-PadPC7)") (class "Default")
      (node (ref "U$1") (pin "PC7") (pinfunction "PC7_PC7") (pintype "bidirectional"))
    )
    (net (code "75") (name "unconnected-(U$1-PadPC8)") (class "Default")
      (node (ref "U$1") (pin "PC8") (pinfunction "PC8_PC8") (pintype "bidirectional"))
    )
    (net (code "76") (name "unconnected-(U$1-PadPC9)") (class "Default")
      (node (ref "U$1") (pin "PC9") (pinfunction "PC9_PC9") (pintype "bidirectional"))
    )
    (net (code "77") (name "unconnected-(U$1-PadPC10)") (class "Default")
      (node (ref "U$1") (pin "PC10") (pinfunction "PC10_PC10") (pintype "bidirectional"))
    )
    (net (code "78") (name "unconnected-(U$1-PadPC12)") (class "Default")
      (node (ref "U$1") (pin "PC12") (pinfunction "PC12_PC12") (pintype "bidirectional"))
    )
    (net (code "79") (name "unconnected-(U$1-PadPC13)") (class "Default")
      (node (ref "U$1") (pin "PC13") (pinfunction "PC13_PC13") (pintype "bidirectional"))
    )
    (net (code "80") (name "unconnected-(U$1-PadPD2)") (class "Default")
      (node (ref "U$1") (pin "PD2") (pinfunction "PD2_PD2") (pintype "bidirectional"))
    )
    (net (code "81") (name "unconnected-(U$1-PadPH0)") (class "Default")
      (node (ref "U$1") (pin "PH0") (pinfunction "PH0_PH0") (pintype "bidirectional"))
    )
    (net (code "82") (name "unconnected-(U$1-PadPH1)") (class "Default")
      (node (ref "U$1") (pin "PH1") (pinfunction "PH1_PH1") (pintype "bidirectional"))
    )
    (net (code "83") (name "unconnected-(U$1-PadVDD_3)") (class "Default")
      (node (ref "U$1") (pin "VDD_3") (pinfunction "VDD_3_VDD_3") (pintype "bidirectional"))
    )
    (net (code "84") (name "unconnected-(U$1-PadVSS_1)") (class "Default")
      (node (ref "U$1") (pin "VSS_1") (pinfunction "VSS_1_VSS_1") (pintype "bidirectional"))
    )
  )
)
